# ESP-TX.net
KiCad netlist of a schematic drawn in Altium Designer
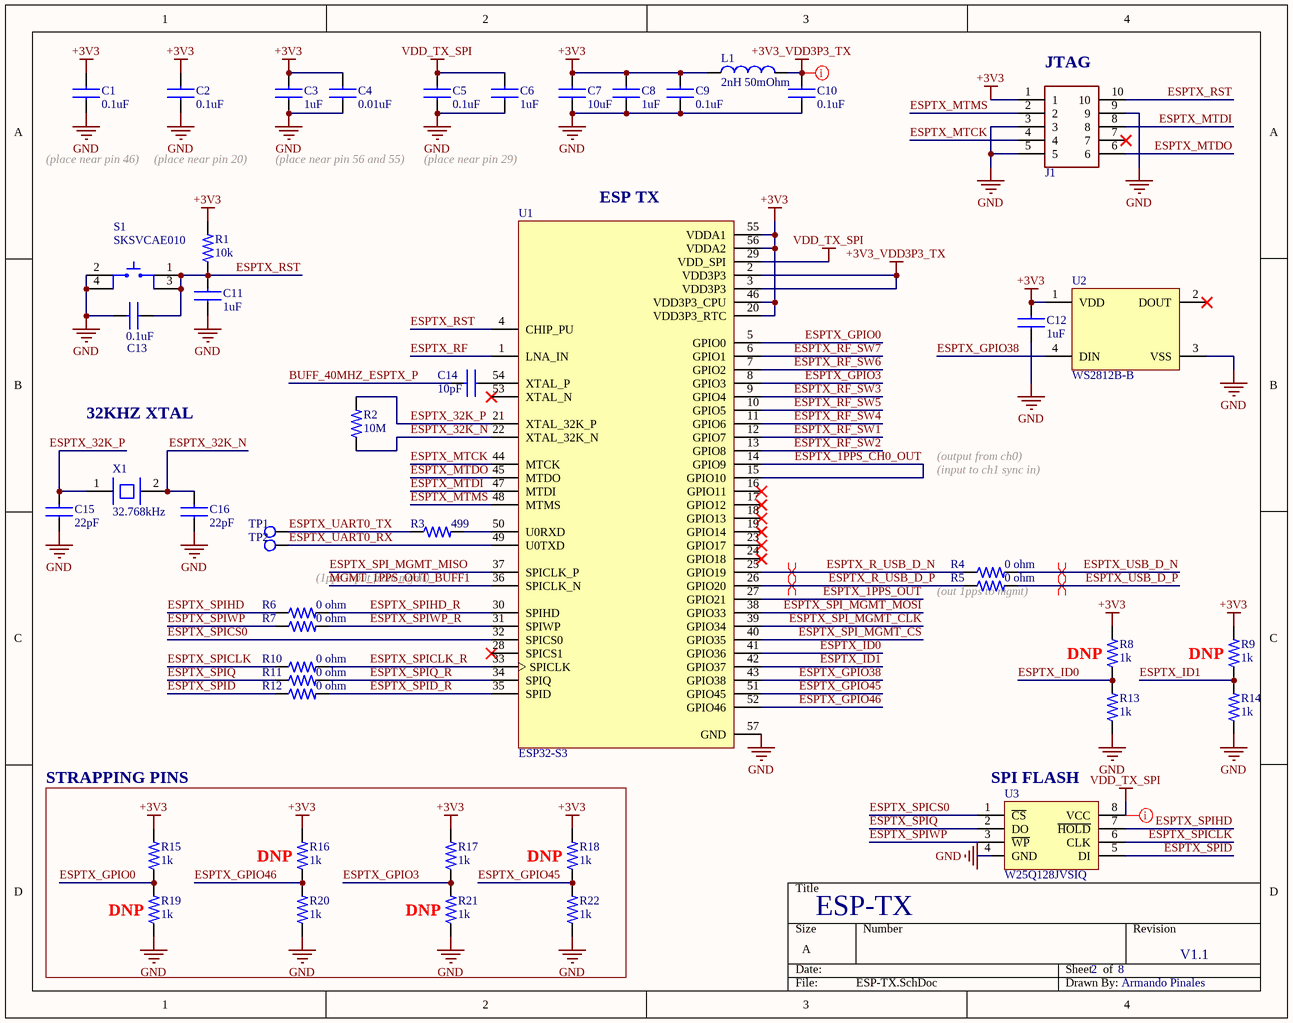
[diagram p0: ESP-TX.SchDoc]

(export (version "E")
  (design (tool "Eeschema 10.0.6"))
  (components
    (comp (ref "C1")
      (value "0.1uF")
      (footprint "CAP_0402")
      (description "Cap Ceramic 0.1uF 16V X7R 10% SMD 0402 125C Paper T/R")
      (fields
        (field (name "MANUFACTURER") "Murata")
        (field (name "MANUFACTURER PART NUMBER") "GCM155R71C104KA55J")
      )
      (libsource (lib "LotusSound") (part "CAP_GCM155R71C104KA55J"))
    )
    (comp (ref "C2")
      (value "0.1uF")
      (footprint "CAP_0402")
      (description "Cap Ceramic 0.1uF 16V X7R 10% SMD 0402 125C Paper T/R")
      (fields
        (field (name "MANUFACTURER") "Murata")
        (field (name "MANUFACTURER PART NUMBER") "GCM155R71C104KA55J")
      )
      (libsource (lib "LotusSound") (part "CAP_GCM155R71C104KA55J"))
    )
    (comp (ref "C3")
      (value "1uF")
      (footprint "CAP_0402")
      (description "Cap Ceramic 1uF 25V X5R 10% SMD 0402 85°C Cardboard T/R")
      (fields
        (field (name "MANUFACTURER") "Samsung")
        (field (name "MANUFACTURER PART NUMBER") "CL05A105KA5NQNC")
      )
      (libsource (lib "LotusSound") (part "CAP_CL05A105KA5NQNC"))
    )
    (comp (ref "C4")
      (value "0.01uF")
      (footprint "CAP_0402")
      (description "Cap Ceramic 0.01uF 50V X7R 10% Pad SMD 0402 125°C T/R")
      (fields
        (field (name "MANUFACTURER") "Yageo")
        (field (name "MANUFACTURER PART NUMBER") "CC0402KRX7R9BB103")
      )
      (libsource (lib "LotusSound") (part "CAP_CC0402KRX7R9BB103"))
    )
    (comp (ref "C5")
      (value "0.1uF")
      (footprint "CAP_0402")
      (description "Cap Ceramic 0.1uF 16V X7R 10% SMD 0402 125C Paper T/R")
      (fields
        (field (name "MANUFACTURER") "Murata")
        (field (name "MANUFACTURER PART NUMBER") "GCM155R71C104KA55J")
      )
      (libsource (lib "LotusSound") (part "CAP_GCM155R71C104KA55J"))
    )
    (comp (ref "C6")
      (value "1uF")
      (footprint "CAP_0402")
      (description "Cap Ceramic 1uF 25V X5R 10% SMD 0402 85°C Cardboard T/R")
      (fields
        (field (name "MANUFACTURER") "Samsung")
        (field (name "MANUFACTURER PART NUMBER") "CL05A105KA5NQNC")
      )
      (libsource (lib "LotusSound") (part "CAP_CL05A105KA5NQNC"))
    )
    (comp (ref "C7")
      (value "10uF")
      (footprint "CAP_0402")
      (description "Cap Ceramic 10uF 6.3V X5R 20% SMD 0402 85°C Paper T/R")
      (fields
        (field (name "MANUFACTURER") "Samsung")
        (field (name "MANUFACTURER PART NUMBER") "CL05A106MQ5NUNC")
      )
      (libsource (lib "LotusSound") (part "CAP_CL05A106MQ5NUNC"))
    )
    (comp (ref "C8")
      (value "1uF")
      (footprint "CAP_0402")
      (description "Cap Ceramic 1uF 25V X5R 10% SMD 0402 85°C Cardboard T/R")
      (fields
        (field (name "MANUFACTURER") "Samsung")
        (field (name "MANUFACTURER PART NUMBER") "CL05A105KA5NQNC")
      )
      (libsource (lib "LotusSound") (part "CAP_CL05A105KA5NQNC"))
    )
    (comp (ref "C9")
      (value "0.1uF")
      (footprint "CAP_0402")
      (description "Cap Ceramic 0.1uF 16V X7R 10% SMD 0402 125C Paper T/R")
      (fields
        (field (name "MANUFACTURER") "Murata")
        (field (name "MANUFACTURER PART NUMBER") "GCM155R71C104KA55J")
      )
      (libsource (lib "LotusSound") (part "CAP_GCM155R71C104KA55J"))
    )
    (comp (ref "C10")
      (value "0.1uF")
      (footprint "CAP_0402")
      (description "Cap Ceramic 0.1uF 16V X7R 10% SMD 0402 125C Paper T/R")
      (fields
        (field (name "MANUFACTURER") "Murata")
        (field (name "MANUFACTURER PART NUMBER") "GCM155R71C104KA55J")
      )
      (libsource (lib "LotusSound") (part "CAP_GCM155R71C104KA55J"))
    )
    (comp (ref "C11")
      (value "1uF")
      (footprint "CAP_0402")
      (description "Cap Ceramic 1uF 25V X5R 10% SMD 0402 85°C Cardboard T/R")
      (fields
        (field (name "MANUFACTURER") "Samsung")
        (field (name "MANUFACTURER PART NUMBER") "CL05A105KA5NQNC")
      )
      (libsource (lib "LotusSound") (part "CAP_CL05A105KA5NQNC"))
    )
    (comp (ref "C12")
      (value "1uF")
      (footprint "CAP_0402")
      (description "Cap Ceramic 1uF 25V X5R 10% SMD 0402 85°C Cardboard T/R")
      (fields
        (field (name "MANUFACTURER") "Samsung")
        (field (name "MANUFACTURER PART NUMBER") "CL05A105KA5NQNC")
      )
      (libsource (lib "LotusSound") (part "CAP_CL05A105KA5NQNC"))
    )
    (comp (ref "C13")
      (value "0.1uF")
      (footprint "CAP_0402")
      (description "Cap Ceramic 0.1uF 16V X7R 10% SMD 0402 125C Paper T/R")
      (fields
        (field (name "MANUFACTURER") "Murata")
        (field (name "MANUFACTURER PART NUMBER") "GCM155R71C104KA55J")
      )
      (libsource (lib "LotusSound") (part "CAP_GCM155R71C104KA55J"))
    )
    (comp (ref "C14")
      (value "10pF")
      (footprint "CAP_0402")
      (description "Cap Ceramic 10pF 50V C0G 0.5pF Pad SMD 0402 150C Automotive T/R")
      (fields
        (field (name "MANUFACTURER") "TDK")
        (field (name "MANUFACTURER PART NUMBER") "CGA2B2NP01H100D050BA")
      )
      (libsource (lib "LotusSound") (part "CAP_CGA2B2NP01H100D050BA"))
    )
    (comp (ref "C15")
      (value "22pF")
      (footprint "CAP_0402")
      (description "0402 22 pF 50 V ±5 % Tolerance NP0 SMT Multilayer Ceramic Capacitor")
      (fields
        (field (name "MANUFACTURER") "Yageo")
        (field (name "MANUFACTURER PART NUMBER") "CC0402JRNPO9BN220")
      )
      (libsource (lib "LotusSound") (part "CAP_CC0402JRNPO9BN220"))
    )
    (comp (ref "C16")
      (value "22pF")
      (footprint "CAP_0402")
      (description "0402 22 pF 50 V ±5 % Tolerance NP0 SMT Multilayer Ceramic Capacitor")
      (fields
        (field (name "MANUFACTURER") "Yageo")
        (field (name "MANUFACTURER PART NUMBER") "CC0402JRNPO9BN220")
      )
      (libsource (lib "LotusSound") (part "CAP_CC0402JRNPO9BN220"))
    )
    (comp (ref "J1")
      (value "CONN_TC2050-IDC")
      (footprint "CONN_TAG-CONNECT_TC2050-IDC")
      (description "Cbl Plug-Of-Nails 10-Pin w/Legs")
      (fields (field (name "MF") "{'manufacturer': u'Tag-Connect LLC'}") (field (name "MP") "TC2050-IDC"))
      (libsource (lib "LotusSound") (part "CONN_TC2050-IDC"))
    )
    (comp (ref "L1")
      (value "2nH 50mOhm")
      (footprint "IND_INDC1006X60N")
      (description "FIXED IND 2NH 1A 50 MOHM SMD")
      (fields (field (name "MF") "{'manufacturer': u'TDK'}") (field (name "MP") "MHQ1005P2N0STD25"))
      (libsource (lib "LotusSound") (part "IND_MHQ1005P2N0STD25"))
    )
    (comp (ref "R1")
      (value "10k")
      (footprint "RES_0402")
      (description "RES SMD 10K OHM 1% 1/16W 0402")
      (fields
        (field (name "MANUFACTURER") "Yageo")
        (field (name "MANUFACTURER PART NUMBER") "AC0402FR-0710KL")
      )
      (libsource (lib "LotusSound") (part "RES_AC0402FR-0710KL"))
    )
    (comp (ref "R2")
      (value "10M")
      (footprint "RES_0402")
      (description "Res Thick Film 0402 10M Ohm 5% 0.063W(1/16W) ±100ppm/C Pad SMD Automotive T/R")
      (fields
        (field (name "MANUFACTURER") "TE Connectivity")
        (field (name "MANUFACTURER PART NUMBER") "CRGCQ0402J10M")
      )
      (libsource (lib "LotusSound") (part "RES_CRGCQ0402J10M"))
    )
    (comp (ref "R3")
      (value "499")
      (footprint "RES_0402")
      (description "Res General Purpose Thick Film 0402 499 Ohm 1% 1/16W ±100ppm/°C Molded SMD Paper T/R")
      (fields
        (field (name "MANUFACTURER") "Yageo")
        (field (name "MANUFACTURER PART NUMBER") "RC0402FR-07499RL")
      )
      (libsource (lib "LotusSound") (part "RES_RC0402FR-07499RL"))
    )
    (comp (ref "R4")
      (value "0 ohm")
      (footprint "RES_0402")
      (description "RES SMD 0 OHM JUMPER 1/16W 0402")
      (fields
        (field (name "MANUFACTURER") "Yageo")
        (field (name "MANUFACTURER PART NUMBER") "RC0402JR-070RL")
      )
      (libsource (lib "LotusSound") (part "RES_RC0402JR-070RL"))
    )
    (comp (ref "R5")
      (value "0 ohm")
      (footprint "RES_0402")
      (description "RES SMD 0 OHM JUMPER 1/16W 0402")
      (fields
        (field (name "MANUFACTURER") "Yageo")
        (field (name "MANUFACTURER PART NUMBER") "RC0402JR-070RL")
      )
      (libsource (lib "LotusSound") (part "RES_RC0402JR-070RL"))
    )
    (comp (ref "R6")
      (value "0 ohm")
      (footprint "RES_0402")
      (description "RES SMD 0 OHM JUMPER 1/16W 0402")
      (fields
        (field (name "MANUFACTURER") "Yageo")
        (field (name "MANUFACTURER PART NUMBER") "RC0402JR-070RL")
      )
      (libsource (lib "LotusSound") (part "RES_RC0402JR-070RL"))
    )
    (comp (ref "R7")
      (value "0 ohm")
      (footprint "RES_0402")
      (description "RES SMD 0 OHM JUMPER 1/16W 0402")
      (fields
        (field (name "MANUFACTURER") "Yageo")
        (field (name "MANUFACTURER PART NUMBER") "RC0402JR-070RL")
      )
      (libsource (lib "LotusSound") (part "RES_RC0402JR-070RL"))
    )
    (comp (ref "R8")
      (value "1k")
      (footprint "RES_0402")
      (description "Res General Purpose Thick Film 0402 1K Ohm 5% 1/16W ±100ppm/°C Molded SMD Paper T/R")
      (fields
        (field (name "MANUFACTURER") "Yageo")
        (field (name "MANUFACTURER PART NUMBER") "RC0402JR-071KL")
      )
      (libsource (lib "LotusSound") (part "RES_RC0402JR-071KL"))
    )
    (comp (ref "R9")
      (value "1k")
      (footprint "RES_0402")
      (description "Res General Purpose Thick Film 0402 1K Ohm 5% 1/16W ±100ppm/°C Molded SMD Paper T/R")
      (fields
        (field (name "MANUFACTURER") "Yageo")
        (field (name "MANUFACTURER PART NUMBER") "RC0402JR-071KL")
      )
      (libsource (lib "LotusSound") (part "RES_RC0402JR-071KL"))
    )
    (comp (ref "R10")
      (value "0 ohm")
      (footprint "RES_0402")
      (description "RES SMD 0 OHM JUMPER 1/16W 0402")
      (fields
        (field (name "MANUFACTURER") "Yageo")
        (field (name "MANUFACTURER PART NUMBER") "RC0402JR-070RL")
      )
      (libsource (lib "LotusSound") (part "RES_RC0402JR-070RL"))
    )
    (comp (ref "R11")
      (value "0 ohm")
      (footprint "RES_0402")
      (description "RES SMD 0 OHM JUMPER 1/16W 0402")
      (fields
        (field (name "MANUFACTURER") "Yageo")
        (field (name "MANUFACTURER PART NUMBER") "RC0402JR-070RL")
      )
      (libsource (lib "LotusSound") (part "RES_RC0402JR-070RL"))
    )
    (comp (ref "R12")
      (value "0 ohm")
      (footprint "RES_0402")
      (description "RES SMD 0 OHM JUMPER 1/16W 0402")
      (fields
        (field (name "MANUFACTURER") "Yageo")
        (field (name "MANUFACTURER PART NUMBER") "RC0402JR-070RL")
      )
      (libsource (lib "LotusSound") (part "RES_RC0402JR-070RL"))
    )
    (comp (ref "R13")
      (value "1k")
      (footprint "RES_0402")
      (description "Res General Purpose Thick Film 0402 1K Ohm 5% 1/16W ±100ppm/°C Molded SMD Paper T/R")
      (fields
        (field (name "MANUFACTURER") "Yageo")
        (field (name "MANUFACTURER PART NUMBER") "RC0402JR-071KL")
      )
      (libsource (lib "LotusSound") (part "RES_RC0402JR-071KL"))
    )
    (comp (ref "R14")
      (value "1k")
      (footprint "RES_0402")
      (description "Res General Purpose Thick Film 0402 1K Ohm 5% 1/16W ±100ppm/°C Molded SMD Paper T/R")
      (fields
        (field (name "MANUFACTURER") "Yageo")
        (field (name "MANUFACTURER PART NUMBER") "RC0402JR-071KL")
      )
      (libsource (lib "LotusSound") (part "RES_RC0402JR-071KL"))
    )
    (comp (ref "R15")
      (value "1k")
      (footprint "RES_0402")
      (description "Res General Purpose Thick Film 0402 1K Ohm 5% 1/16W ±100ppm/°C Molded SMD Paper T/R")
      (fields
        (field (name "MANUFACTURER") "Yageo")
        (field (name "MANUFACTURER PART NUMBER") "RC0402JR-071KL")
      )
      (libsource (lib "LotusSound") (part "RES_RC0402JR-071KL"))
    )
    (comp (ref "R16")
      (value "1k")
      (footprint "RES_0402")
      (description "Res General Purpose Thick Film 0402 1K Ohm 5% 1/16W ±100ppm/°C Molded SMD Paper T/R")
      (fields
        (field (name "MANUFACTURER") "Yageo")
        (field (name "MANUFACTURER PART NUMBER") "RC0402JR-071KL")
      )
      (libsource (lib "LotusSound") (part "RES_RC0402JR-071KL"))
    )
    (comp (ref "R17")
      (value "1k")
      (footprint "RES_0402")
      (description "Res General Purpose Thick Film 0402 1K Ohm 5% 1/16W ±100ppm/°C Molded SMD Paper T/R")
      (fields
        (field (name "MANUFACTURER") "Yageo")
        (field (name "MANUFACTURER PART NUMBER") "RC0402JR-071KL")
      )
      (libsource (lib "LotusSound") (part "RES_RC0402JR-071KL"))
    )
    (comp (ref "R18")
      (value "1k")
      (footprint "RES_0402")
      (description "Res General Purpose Thick Film 0402 1K Ohm 5% 1/16W ±100ppm/°C Molded SMD Paper T/R")
      (fields
        (field (name "MANUFACTURER") "Yageo")
        (field (name "MANUFACTURER PART NUMBER") "RC0402JR-071KL")
      )
      (libsource (lib "LotusSound") (part "RES_RC0402JR-071KL"))
    )
    (comp (ref "R19")
      (value "1k")
      (footprint "RES_0402")
      (description "Res General Purpose Thick Film 0402 1K Ohm 5% 1/16W ±100ppm/°C Molded SMD Paper T/R")
      (fields
        (field (name "MANUFACTURER") "Yageo")
        (field (name "MANUFACTURER PART NUMBER") "RC0402JR-071KL")
      )
      (libsource (lib "LotusSound") (part "RES_RC0402JR-071KL"))
    )
    (comp (ref "R20")
      (value "1k")
      (footprint "RES_0402")
      (description "Res General Purpose Thick Film 0402 1K Ohm 5% 1/16W ±100ppm/°C Molded SMD Paper T/R")
      (fields
        (field (name "MANUFACTURER") "Yageo")
        (field (name "MANUFACTURER PART NUMBER") "RC0402JR-071KL")
      )
      (libsource (lib "LotusSound") (part "RES_RC0402JR-071KL"))
    )
    (comp (ref "R21")
      (value "1k")
      (footprint "RES_0402")
      (description "Res General Purpose Thick Film 0402 1K Ohm 5% 1/16W ±100ppm/°C Molded SMD Paper T/R")
      (fields
        (field (name "MANUFACTURER") "Yageo")
        (field (name "MANUFACTURER PART NUMBER") "RC0402JR-071KL")
      )
      (libsource (lib "LotusSound") (part "RES_RC0402JR-071KL"))
    )
    (comp (ref "R22")
      (value "1k")
      (footprint "RES_0402")
      (description "Res General Purpose Thick Film 0402 1K Ohm 5% 1/16W ±100ppm/°C Molded SMD Paper T/R")
      (fields
        (field (name "MANUFACTURER") "Yageo")
        (field (name "MANUFACTURER PART NUMBER") "RC0402JR-071KL")
      )
      (libsource (lib "LotusSound") (part "RES_RC0402JR-071KL"))
    )
    (comp (ref "S1")
      (value "SKSVCAE010")
      (footprint "SW_SKSVCAE010")
      (description "2.8x1.9mm Compact Type with Projection Surface Mount SKSV Series Tact Switch")
      (fields (field (name "MANUFACTURER") "Alps Electric"))
      (libsource (lib "LotusSound") (part "SW_SKSVCAE010"))
    )
    (comp (ref "TP1")
      (value "Test Point 1MM")
      (footprint "TP_PAD-1MM")
      (libsource (lib "LotusSound") (part "TP_PAD-1MM"))
    )
    (comp (ref "TP2")
      (value "Test Point 1MM")
      (footprint "TP_PAD-1MM")
      (libsource (lib "LotusSound") (part "TP_PAD-1MM"))
    )
    (comp (ref "U1")
      (value "ESP32-S3")
      (footprint "IC_ESP32-S3")
      (fields (field (name "MF") "Espressif Systems"))
      (libsource (lib "LotusSound") (part "IC_ESP32-S3"))
    )
    (comp (ref "U2")
      (value "WS2812B-B")
      (footprint "LED_WS2812B-B")
      (description "Intelligent control LED integrated light source")
      (fields
        (field (name "MANUFACTURER") "WORLDSEMI")
        (field (name "MANUFACTURER PART NUMBER") "WS2812B-B/W")
      )
      (libsource (lib "LotusSound") (part "LED_WS2812B-B"))
    )
    (comp (ref "U3")
      (value "W25Q128JVSIQ")
      (footprint "IC_W25Q128JVSIQ")
      (description "NOR Flash Serial (SPI, Dual SPI, Quad SPI) 3.3V 128M-bit 16M x 8 6ns 8-Pin SOIC Tube")
      (fields (field (name "MANUFACTURER") "Winbond"))
      (libsource (lib "LotusSound") (part "IC_W25Q128JVSIQ"))
    )
    (comp (ref "X1")
      (value "32.768kHz")
      (footprint "XTAL_X321532768KGD2SI")
      (description "贴片无源晶振 32.768KHZ 12.5PF ±20ppm –40~+85 ℃")
      (fields
        (field (name "MANUFACTURER") "YXC")
        (field (name "MANUFACTURER PART NUMBER") "X321532768KGD2SI")
      )
      (libsource (lib "LotusSound") (part "XTAL_X321532768KGD2SI"))
    )
  )
  (nets
    (net (code "1") (name "+3V3") (class "Default")
      (node (ref "C1") (pin "2") (pinfunction "2_2") (pintype "passive"))
      (node (ref "C12") (pin "2") (pinfunction "2_2") (pintype "passive"))
      (node (ref "C2") (pin "2") (pinfunction "2_2") (pintype "passive"))
      (node (ref "C3") (pin "2") (pinfunction "2_2") (pintype "passive"))
      (node (ref "C4") (pin "2") (pinfunction "2_2") (pintype "passive"))
      (node (ref "C7") (pin "2") (pinfunction "2_2") (pintype "passive"))
      (node (ref "C8") (pin "2") (pinfunction "2_2") (pintype "passive"))
      (node (ref "C9") (pin "2") (pinfunction "2_2") (pintype "passive"))
      (node (ref "J1") (pin "1") (pinfunction "1_1") (pintype "passive"))
      (node (ref "L1") (pin "1") (pinfunction "1_1") (pintype "passive"))
      (node (ref "R1") (pin "2") (pinfunction "2_2") (pintype "passive"))
      (node (ref "R15") (pin "2") (pinfunction "2_2") (pintype "passive"))
      (node (ref "R16") (pin "2") (pinfunction "2_2") (pintype "passive"))
      (node (ref "R17") (pin "2") (pinfunction "2_2") (pintype "passive"))
      (node (ref "R18") (pin "2") (pinfunction "2_2") (pintype "passive"))
      (node (ref "R8") (pin "2") (pinfunction "2_2") (pintype "passive"))
      (node (ref "R9") (pin "2") (pinfunction "2_2") (pintype "passive"))
      (node (ref "U1") (pin "20") (pinfunction "VDD3P3_RTC_20") (pintype "passive"))
      (node (ref "U1") (pin "46") (pinfunction "VDD3P3_CPU_46") (pintype "passive"))
      (node (ref "U1") (pin "55") (pinfunction "VDDA1_55") (pintype "power_in"))
      (node (ref "U1") (pin "56") (pinfunction "VDDA2_56") (pintype "passive"))
      (node (ref "U2") (pin "1") (pinfunction "VDD_1") (pintype "power_in"))
    )
    (net (code "2") (name "+3V3_VDD3P3_TX") (class "Default")
      (node (ref "C10") (pin "2") (pinfunction "2_2") (pintype "passive"))
      (node (ref "L1") (pin "2") (pinfunction "2_2") (pintype "passive"))
      (node (ref "U1") (pin "2") (pinfunction "VDD3P3_2") (pintype "passive"))
      (node (ref "U1") (pin "3") (pinfunction "VDD3P3_3") (pintype "passive"))
    )
    (net (code "3") (name "/BUFF_40MHZ_ESPTX_P") (class "Default")
      (node (ref "C14") (pin "1") (pinfunction "1_1") (pintype "passive"))
    )
    (net (code "4") (name "/ESPTX_1PPS_CH0_OUT") (class "Default")
      (node (ref "U1") (pin "14") (pinfunction "GPIO9_14") (pintype "passive"))
      (node (ref "U1") (pin "15") (pinfunction "GPIO10_15") (pintype "passive"))
    )
    (net (code "5") (name "/ESPTX_1PPS_OUT") (class "Default")
      (node (ref "U1") (pin "27") (pinfunction "GPIO21_27") (pintype "passive"))
    )
    (net (code "6") (name "/ESPTX_32K_N") (class "Default")
      (node (ref "C16") (pin "2") (pinfunction "2_2") (pintype "passive"))
      (node (ref "R2") (pin "1") (pinfunction "1_1") (pintype "passive"))
      (node (ref "U1") (pin "22") (pinfunction "XTAL_32K_N_22") (pintype "passive"))
      (node (ref "X1") (pin "2") (pinfunction "GND_2") (pintype "power_in"))
    )
    (net (code "7") (name "/ESPTX_32K_P") (class "Default")
      (node (ref "C15") (pin "2") (pinfunction "2_2") (pintype "passive"))
      (node (ref "R2") (pin "2") (pinfunction "2_2") (pintype "passive"))
      (node (ref "U1") (pin "21") (pinfunction "XTAL_32K_P_21") (pintype "passive"))
      (node (ref "X1") (pin "1") (pinfunction "IN/OUT_1") (pintype "passive"))
    )
    (net (code "8") (name "/ESPTX_GPIO0") (class "Default")
      (node (ref "R15") (pin "1") (pinfunction "1_1") (pintype "passive"))
      (node (ref "R19") (pin "2") (pinfunction "2_2") (pintype "passive"))
      (node (ref "U1") (pin "5") (pinfunction "GPIO0_5") (pintype "passive"))
    )
    (net (code "9") (name "/ESPTX_GPIO3") (class "Default")
      (node (ref "R17") (pin "1") (pinfunction "1_1") (pintype "passive"))
      (node (ref "R21") (pin "2") (pinfunction "2_2") (pintype "passive"))
      (node (ref "U1") (pin "8") (pinfunction "GPIO3_8") (pintype "passive"))
    )
    (net (code "10") (name "/ESPTX_GPIO38") (class "Default")
      (node (ref "U1") (pin "43") (pinfunction "GPIO38_43") (pintype "passive"))
      (node (ref "U2") (pin "4") (pinfunction "DIN_4") (pintype "passive"))
    )
    (net (code "11") (name "/ESPTX_GPIO45") (class "Default")
      (node (ref "R18") (pin "1") (pinfunction "1_1") (pintype "passive"))
      (node (ref "R22") (pin "2") (pinfunction "2_2") (pintype "passive"))
      (node (ref "U1") (pin "51") (pinfunction "GPIO45_51") (pintype "passive"))
    )
    (net (code "12") (name "/ESPTX_GPIO46") (class "Default")
      (node (ref "R16") (pin "1") (pinfunction "1_1") (pintype "passive"))
      (node (ref "R20") (pin "2") (pinfunction "2_2") (pintype "passive"))
      (node (ref "U1") (pin "52") (pinfunction "GPIO46_52") (pintype "passive"))
    )
    (net (code "13") (name "/ESPTX_ID0") (class "Default")
      (node (ref "R13") (pin "2") (pinfunction "2_2") (pintype "passive"))
      (node (ref "R8") (pin "1") (pinfunction "1_1") (pintype "passive"))
      (node (ref "U1") (pin "41") (pinfunction "GPIO36_41") (pintype "passive"))
    )
    (net (code "14") (name "/ESPTX_ID1") (class "Default")
      (node (ref "R14") (pin "2") (pinfunction "2_2") (pintype "passive"))
      (node (ref "R9") (pin "1") (pinfunction "1_1") (pintype "passive"))
      (node (ref "U1") (pin "42") (pinfunction "GPIO37_42") (pintype "passive"))
    )
    (net (code "15") (name "/ESPTX_MTCK") (class "Default")
      (node (ref "J1") (pin "4") (pinfunction "4_4") (pintype "passive"))
      (node (ref "U1") (pin "44") (pinfunction "MTCK_44") (pintype "passive"))
    )
    (net (code "16") (name "/ESPTX_MTDI") (class "Default")
      (node (ref "J1") (pin "8") (pinfunction "8_8") (pintype "passive"))
      (node (ref "U1") (pin "47") (pinfunction "MTDI_47") (pintype "passive"))
    )
    (net (code "17") (name "/ESPTX_MTDO") (class "Default")
      (node (ref "J1") (pin "6") (pinfunction "6_6") (pintype "passive"))
      (node (ref "U1") (pin "45") (pinfunction "MTDO_45") (pintype "passive"))
    )
    (net (code "18") (name "/ESPTX_MTMS") (class "Default")
      (node (ref "J1") (pin "2") (pinfunction "2_2") (pintype "passive"))
      (node (ref "U1") (pin "48") (pinfunction "MTMS_48") (pintype "passive"))
    )
    (net (code "19") (name "/ESPTX_RF") (class "Default")
      (node (ref "U1") (pin "1") (pinfunction "LNA_IN_1") (pintype "passive"))
    )
    (net (code "20") (name "/ESPTX_RF_SW1") (class "Default")
      (node (ref "U1") (pin "12") (pinfunction "GPIO7_12") (pintype "passive"))
    )
    (net (code "21") (name "/ESPTX_RF_SW2") (class "Default")
      (node (ref "U1") (pin "13") (pinfunction "GPIO8_13") (pintype "passive"))
    )
    (net (code "22") (name "/ESPTX_RF_SW3") (class "Default")
      (node (ref "U1") (pin "9") (pinfunction "GPIO4_9") (pintype "passive"))
    )
    (net (code "23") (name "/ESPTX_RF_SW4") (class "Default")
      (node (ref "U1") (pin "11") (pinfunction "GPIO6_11") (pintype "passive"))
    )
    (net (code "24") (name "/ESPTX_RF_SW5") (class "Default")
      (node (ref "U1") (pin "10") (pinfunction "GPIO5_10") (pintype "passive"))
    )
    (net (code "25") (name "/ESPTX_RF_SW6") (class "Default")
      (node (ref "U1") (pin "7") (pinfunction "GPIO2_7") (pintype "passive"))
    )
    (net (code "26") (name "/ESPTX_RF_SW7") (class "Default")
      (node (ref "U1") (pin "6") (pinfunction "GPIO1_6") (pintype "passive"))
    )
    (net (code "27") (name "/ESPTX_RST") (class "Default")
      (node (ref "C11") (pin "2") (pinfunction "2_2") (pintype "passive"))
      (node (ref "C13") (pin "2") (pinfunction "2_2") (pintype "passive"))
      (node (ref "J1") (pin "10") (pinfunction "10_10") (pintype "passive"))
      (node (ref "R1") (pin "1") (pinfunction "1_1") (pintype "passive"))
      (node (ref "S1") (pin "1") (pinfunction "1_1") (pintype "passive"))
      (node (ref "S1") (pin "3") (pinfunction "3_3") (pintype "passive"))
      (node (ref "U1") (pin "4") (pinfunction "CHIP_PU_4") (pintype "passive"))
    )
    (net (code "28") (name "/ESPTX_R_USB_D_N") (class "Default")
      (node (ref "R4") (pin "1") (pinfunction "1_1") (pintype "passive"))
      (node (ref "U1") (pin "25") (pinfunction "GPIO19_25") (pintype "passive"))
    )
    (net (code "29") (name "/ESPTX_R_USB_D_P") (class "Default")
      (node (ref "R5") (pin "1") (pinfunction "1_1") (pintype "passive"))
      (node (ref "U1") (pin "26") (pinfunction "GPIO20_26") (pintype "passive"))
    )
    (net (code "30") (name "/ESPTX_SPICLK") (class "Default")
      (node (ref "R10") (pin "1") (pinfunction "1_1") (pintype "passive"))
      (node (ref "U3") (pin "6") (pinfunction "CLK_6") (pintype "passive"))
    )
    (net (code "31") (name "/ESPTX_SPICLK_R") (class "Default")
      (node (ref "R10") (pin "2") (pinfunction "2_2") (pintype "passive"))
      (node (ref "U1") (pin "33") (pinfunction "SPICLK_33") (pintype "passive"))
    )
    (net (code "32") (name "/ESPTX_SPICS0") (class "Default")
      (node (ref "U1") (pin "32") (pinfunction "SPICS0_32") (pintype "passive"))
      (node (ref "U3") (pin "1") (pinfunction "~{CS}_1") (pintype "passive"))
    )
    (net (code "33") (name "/ESPTX_SPID") (class "Default")
      (node (ref "R12") (pin "1") (pinfunction "1_1") (pintype "passive"))
      (node (ref "U3") (pin "5") (pinfunction "DI_5") (pintype "passive"))
    )
    (net (code "34") (name "/ESPTX_SPID_R") (class "Default")
      (node (ref "R12") (pin "2") (pinfunction "2_2") (pintype "passive"))
      (node (ref "U1") (pin "35") (pinfunction "SPID_35") (pintype "passive"))
    )
    (net (code "35") (name "/ESPTX_SPIHD") (class "Default")
      (node (ref "R6") (pin "1") (pinfunction "1_1") (pintype "passive"))
      (node (ref "U3") (pin "7") (pinfunction "~{HOLD}_7") (pintype "passive"))
    )
    (net (code "36") (name "/ESPTX_SPIHD_R") (class "Default")
      (node (ref "R6") (pin "2") (pinfunction "2_2") (pintype "passive"))
      (node (ref "U1") (pin "30") (pinfunction "SPIHD_30") (pintype "passive"))
    )
    (net (code "37") (name "/ESPTX_SPIQ") (class "Default")
      (node (ref "R11") (pin "1") (pinfunction "1_1") (pintype "passive"))
      (node (ref "U3") (pin "2") (pinfunction "DO_2") (pintype "passive"))
    )
    (net (code "38") (name "/ESPTX_SPIQ_R") (class "Default")
      (node (ref "R11") (pin "2") (pinfunction "2_2") (pintype "passive"))
      (node (ref "U1") (pin "34") (pinfunction "SPIQ_34") (pintype "passive"))
    )
    (net (code "39") (name "/ESPTX_SPIWP") (class "Default")
      (node (ref "R7") (pin "1") (pinfunction "1_1") (pintype "passive"))
      (node (ref "U3") (pin "3") (pinfunction "~{WP}_3") (pintype "passive"))
    )
    (net (code "40") (name "/ESPTX_SPIWP_R") (class "Default")
      (node (ref "R7") (pin "2") (pinfunction "2_2") (pintype "passive"))
      (node (ref "U1") (pin "31") (pinfunction "SPIWP_31") (pintype "passive"))
    )
    (net (code "41") (name "/ESPTX_SPI_MGMT_CLK") (class "Default")
      (node (ref "U1") (pin "39") (pinfunction "GPIO34_39") (pintype "passive"))
    )
    (net (code "42") (name "/ESPTX_SPI_MGMT_CS") (class "Default")
      (node (ref "U1") (pin "40") (pinfunction "GPIO35_40") (pintype "passive"))
    )
    (net (code "43") (name "/ESPTX_SPI_MGMT_MISO") (class "Default")
      (node (ref "U1") (pin "37") (pinfunction "SPICLK_P_37") (pintype "passive"))
    )
    (net (code "44") (name "/ESPTX_SPI_MGMT_MOSI") (class "Default")
      (node (ref "U1") (pin "38") (pinfunction "GPIO33_38") (pintype "passive"))
    )
    (net (code "45") (name "/ESPTX_UART0_RX") (class "Default")
      (node (ref "TP2") (pin "1") (pinfunction "1_1") (pintype "passive"))
      (node (ref "U1") (pin "49") (pinfunction "U0TXD_49") (pintype "passive"))
    )
    (net (code "46") (name "/ESPTX_UART0_TX") (class "Default")
      (node (ref "R3") (pin "1") (pinfunction "1_1") (pintype "passive"))
      (node (ref "TP1") (pin "1") (pinfunction "1_1") (pintype "passive"))
    )
    (net (code "47") (name "/ESPTX_USB_D_N") (class "Default")
      (node (ref "R4") (pin "2") (pinfunction "2_2") (pintype "passive"))
    )
    (net (code "48") (name "/ESPTX_USB_D_P") (class "Default")
      (node (ref "R5") (pin "2") (pinfunction "2_2") (pintype "passive"))
    )
    (net (code "49") (name "/MGMT_1PPS_OUT_BUFF1") (class "Default")
      (node (ref "U1") (pin "36") (pinfunction "SPICLK_N_36") (pintype "passive"))
    )
    (net (code "50") (name "GND") (class "Default")
      (node (ref "C1") (pin "1") (pinfunction "1_1") (pintype "passive"))
      (node (ref "C10") (pin "1") (pinfunction "1_1") (pintype "passive"))
      (node (ref "C11") (pin "1") (pinfunction "1_1") (pintype "passive"))
      (node (ref "C12") (pin "1") (pinfunction "1_1") (pintype "passive"))
      (node (ref "C13") (pin "1") (pinfunction "1_1") (pintype "passive"))
      (node (ref "C15") (pin "1") (pinfunction "1_1") (pintype "passive"))
      (node (ref "C16") (pin "1") (pinfunction "1_1") (pintype "passive"))
      (node (ref "C2") (pin "1") (pinfunction "1_1") (pintype "passive"))
      (node (ref "C3") (pin "1") (pinfunction "1_1") (pintype "passive"))
      (node (ref "C4") (pin "1") (pinfunction "1_1") (pintype "passive"))
      (node (ref "C5") (pin "1") (pinfunction "1_1") (pintype "passive"))
      (node (ref "C6") (pin "1") (pinfunction "1_1") (pintype "passive"))
      (node (ref "C7") (pin "1") (pinfunction "1_1") (pintype "passive"))
      (node (ref "C8") (pin "1") (pinfunction "1_1") (pintype "passive"))
      (node (ref "C9") (pin "1") (pinfunction "1_1") (pintype "passive"))
      (node (ref "J1") (pin "3") (pinfunction "3_3") (pintype "passive"))
      (node (ref "J1") (pin "5") (pinfunction "5_5") (pintype "passive"))
      (node (ref "J1") (pin "9") (pinfunction "9_9") (pintype "passive"))
      (node (ref "R13") (pin "1") (pinfunction "1_1") (pintype "passive"))
      (node (ref "R14") (pin "1") (pinfunction "1_1") (pintype "passive"))
      (node (ref "R19") (pin "1") (pinfunction "1_1") (pintype "passive"))
      (node (ref "R20") (pin "1") (pinfunction "1_1") (pintype "passive"))
      (node (ref "R21") (pin "1") (pinfunction "1_1") (pintype "passive"))
      (node (ref "R22") (pin "1") (pinfunction "1_1") (pintype "passive"))
      (node (ref "S1") (pin "2") (pinfunction "2_2") (pintype "passive"))
      (node (ref "S1") (pin "4") (pinfunction "4_4") (pintype "passive"))
      (node (ref "U1") (pin "57") (pinfunction "GND_57") (pintype "passive"))
      (node (ref "U2") (pin "3") (pinfunction "VSS_3") (pintype "power_in"))
      (node (ref "U3") (pin "4") (pinfunction "GND_4") (pintype "power_in"))
    )
    (net (code "51") (name "Net-(U1-U0RXD)") (class "Default")
      (node (ref "R3") (pin "2") (pinfunction "2_2") (pintype "passive"))
      (node (ref "U1") (pin "50") (pinfunction "U0RXD_50") (pintype "passive"))
    )
    (net (code "52") (name "Net-(U1-XTAL_P)") (class "Default")
      (node (ref "C14") (pin "2") (pinfunction "2_2") (pintype "passive"))
      (node (ref "U1") (pin "54") (pinfunction "XTAL_P_54") (pintype "passive"))
    )
    (net (code "53") (name "VDD_TX_SPI") (class "Default")
      (node (ref "C5") (pin "2") (pinfunction "2_2") (pintype "passive"))
      (node (ref "C6") (pin "2") (pinfunction "2_2") (pintype "passive"))
      (node (ref "U1") (pin "29") (pinfunction "VDD_SPI_29") (pintype "passive"))
      (node (ref "U3") (pin "8") (pinfunction "VCC_8") (pintype "passive"))
    )
    (net (code "54") (name "unconnected-(J1-Pad7)") (class "Default")
      (node (ref "J1") (pin "7") (pinfunction "7_7") (pintype "passive+no_connect"))
    )
    (net (code "55") (name "unconnected-(U1-GPIO11-Pad16)") (class "Default")
      (node (ref "U1") (pin "16") (pinfunction "GPIO11_16") (pintype "passive+no_connect"))
    )
    (net (code "56") (name "unconnected-(U1-GPIO12-Pad17)") (class "Default")
      (node (ref "U1") (pin "17") (pinfunction "GPIO12_17") (pintype "passive+no_connect"))
    )
    (net (code "57") (name "unconnected-(U1-GPIO13-Pad18)") (class "Default")
      (node (ref "U1") (pin "18") (pinfunction "GPIO13_18") (pintype "passive+no_connect"))
    )
    (net (code "58") (name "unconnected-(U1-GPIO14-Pad19)") (class "Default")
      (node (ref "U1") (pin "19") (pinfunction "GPIO14_19") (pintype "passive+no_connect"))
    )
    (net (code "59") (name "unconnected-(U1-GPIO17-Pad23)") (class "Default")
      (node (ref "U1") (pin "23") (pinfunction "GPIO17_23") (pintype "passive+no_connect"))
    )
    (net (code "60") (name "unconnected-(U1-GPIO18-Pad24)") (class "Default")
      (node (ref "U1") (pin "24") (pinfunction "GPIO18_24") (pintype "passive+no_connect"))
    )
    (net (code "61") (name "unconnected-(U1-SPICS1-Pad28)") (class "Default")
      (node (ref "U1") (pin "28") (pinfunction "SPICS1_28") (pintype "passive+no_connect"))
    )
    (net (code "62") (name "unconnected-(U1-XTAL_N-Pad53)") (class "Default")
      (node (ref "U1") (pin "53") (pinfunction "XTAL_N_53") (pintype "passive+no_connect"))
    )
    (net (code "63") (name "unconnected-(U2-DOUT-Pad2)") (class "Default")
      (node (ref "U2") (pin "2") (pinfunction "DOUT_2") (pintype "passive+no_connect"))
    )
  )
)
